# STM32.net
KiCad netlist of a schematic drawn in Altium Designer
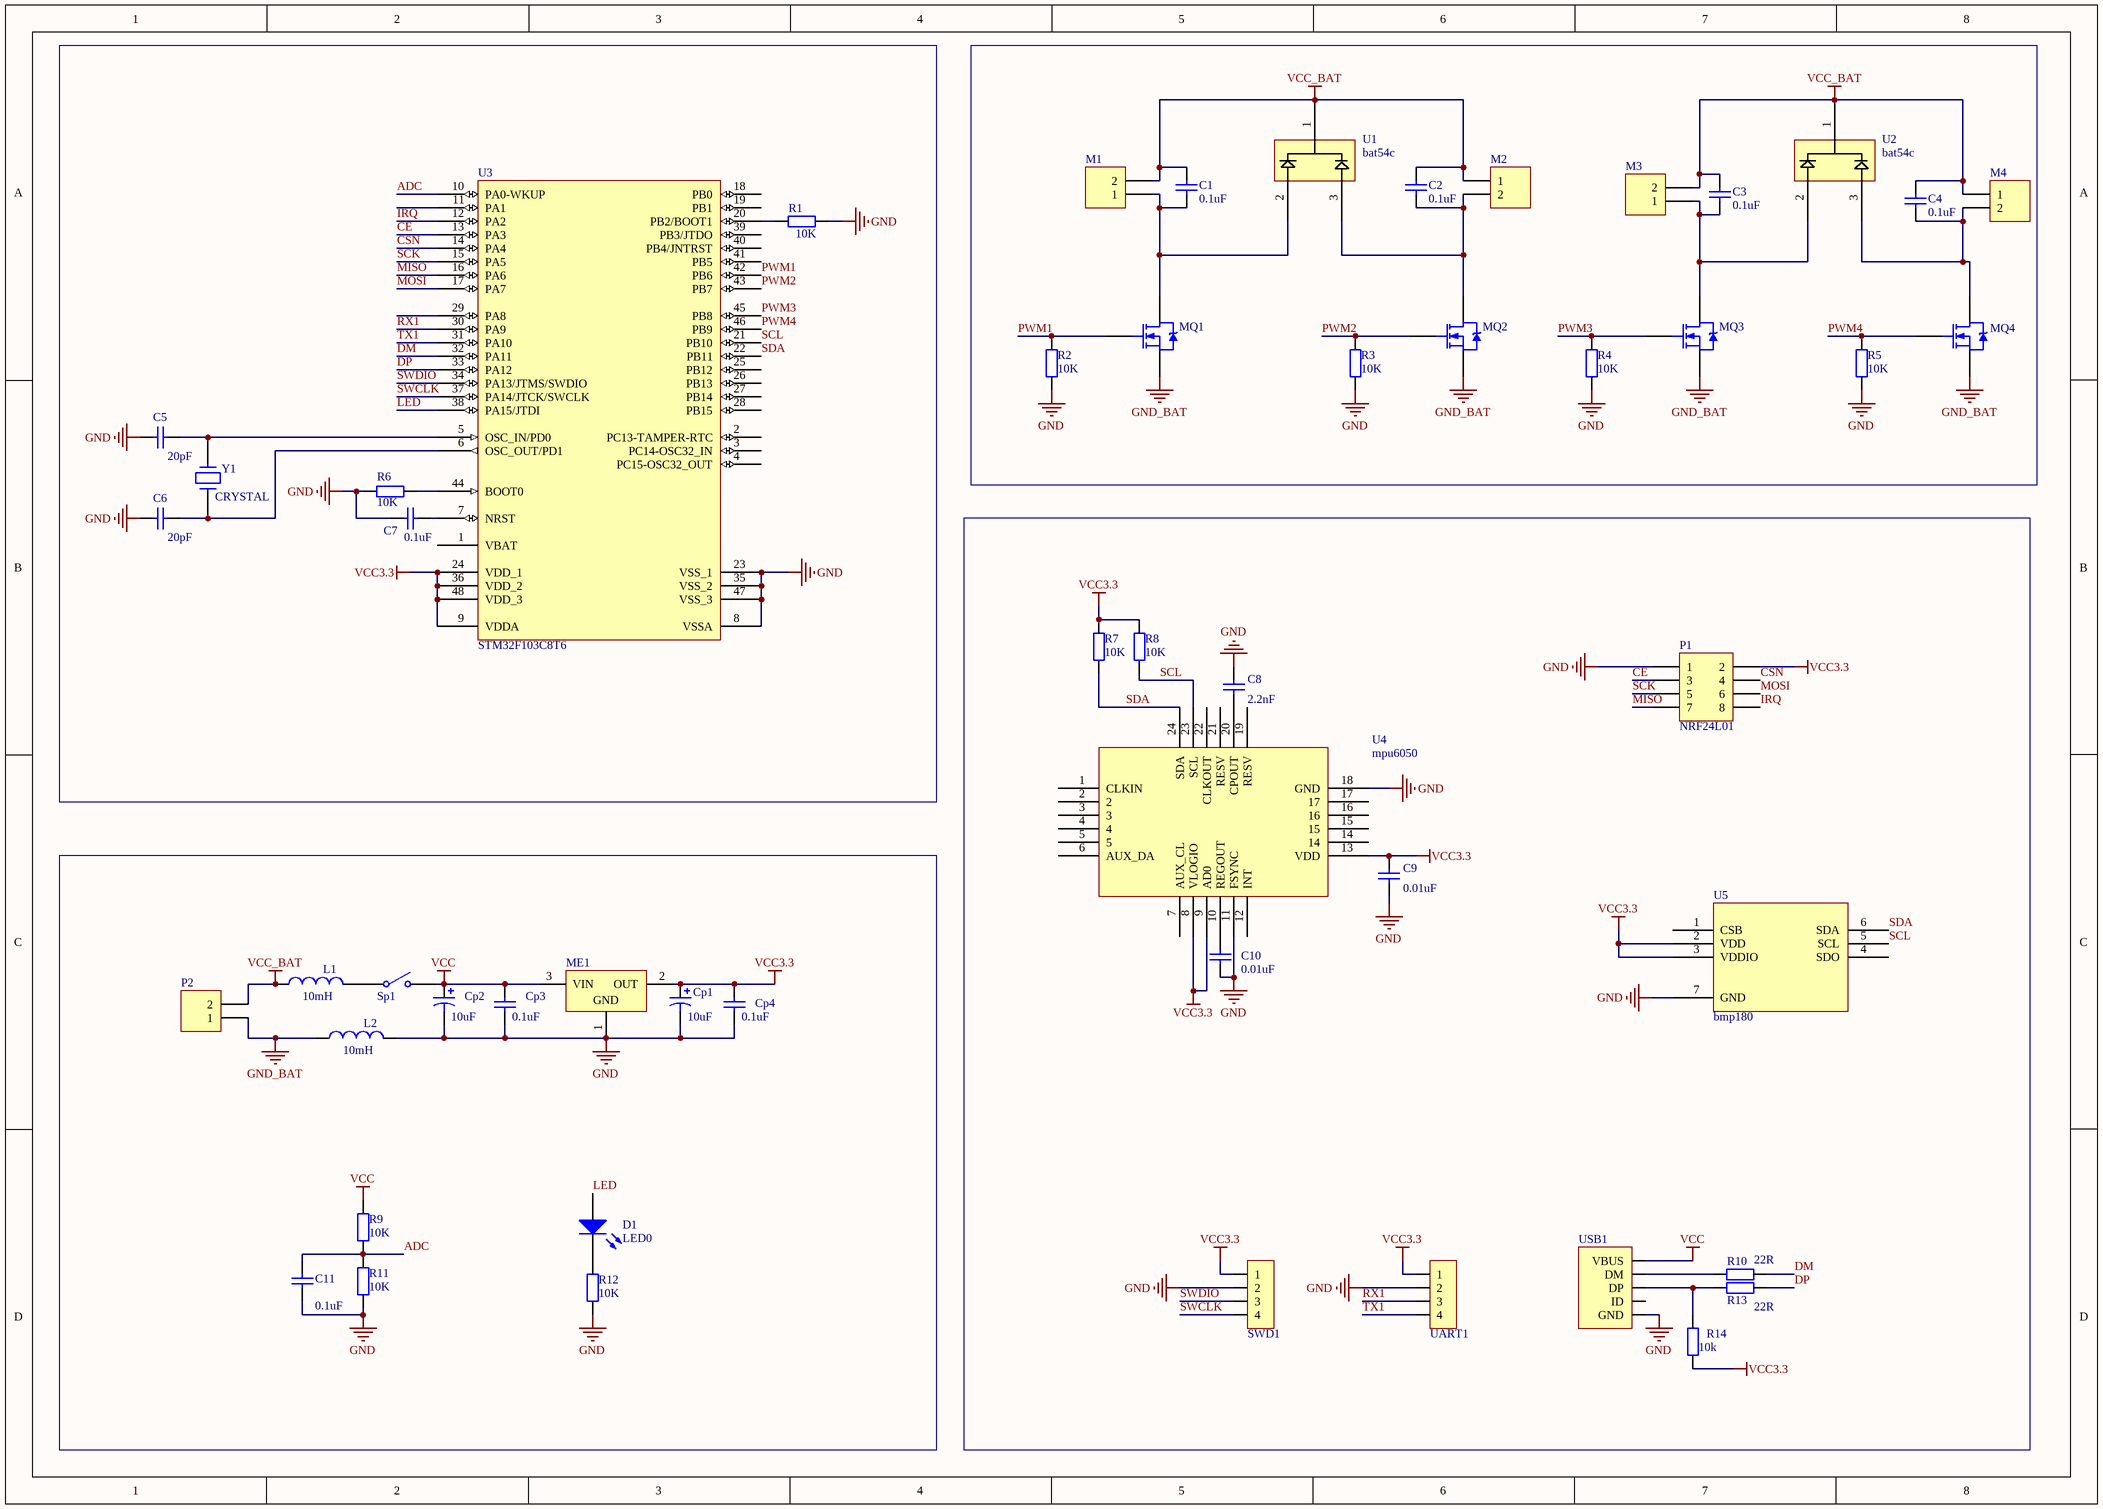
[diagram p0: STM32四轴.SchDoc]

(export (version "E")
  (design (tool "Eeschema 10.0.6"))
  (components
    (comp (ref "C1")
      (value "0.1uF")
      (footprint "0805s")
      (description "Capacitor")
      (fields (field (name "Comment") "Cap") (field (name "PUBLISHER") "Altium Limited"))
      (libsource (lib "Miscellaneous Devices") (part "Cap"))
    )
    (comp (ref "C2")
      (value "0.1uF")
      (footprint "0805s")
      (description "Capacitor")
      (fields (field (name "Comment") "Cap") (field (name "PUBLISHER") "Altium Limited"))
      (libsource (lib "Miscellaneous Devices") (part "Cap"))
    )
    (comp (ref "C3")
      (value "0.1uF")
      (footprint "0805s")
      (description "Capacitor")
      (fields (field (name "Comment") "Cap") (field (name "PUBLISHER") "Altium Limited"))
      (libsource (lib "Miscellaneous Devices") (part "Cap"))
    )
    (comp (ref "C4")
      (value "0.1uF")
      (footprint "0805s")
      (description "Capacitor")
      (fields (field (name "Comment") "Cap") (field (name "PUBLISHER") "Altium Limited"))
      (libsource (lib "Miscellaneous Devices") (part "Cap"))
    )
    (comp (ref "C5")
      (value "20pF")
      (footprint "0805s")
      (description "Capacitor")
      (fields (field (name "Comment") "Cap") (field (name "PUBLISHER") "Altium Limited"))
      (libsource (lib "Miscellaneous Devices") (part "Cap"))
    )
    (comp (ref "C6")
      (value "20pF")
      (footprint "0805s")
      (description "Capacitor")
      (fields (field (name "Comment") "Cap") (field (name "PUBLISHER") "Altium Limited"))
      (libsource (lib "Miscellaneous Devices") (part "Cap"))
    )
    (comp (ref "C7")
      (value "0.1uF")
      (footprint "0805s")
      (description "Capacitor")
      (fields (field (name "Comment") "Cap") (field (name "PUBLISHER") "Altium Limited"))
      (libsource (lib "Miscellaneous Devices") (part "Cap"))
    )
    (comp (ref "C8")
      (value "2.2nF")
      (footprint "0805s")
      (description "Capacitor")
      (fields (field (name "Comment") "Cap") (field (name "PUBLISHER") "Altium Limited"))
      (libsource (lib "Miscellaneous Devices") (part "Cap"))
    )
    (comp (ref "C9")
      (value "0.01uF")
      (footprint "0805s")
      (description "Capacitor")
      (fields (field (name "Comment") "Cap") (field (name "PUBLISHER") "Altium Limited"))
      (libsource (lib "Miscellaneous Devices") (part "Cap"))
    )
    (comp (ref "C10")
      (value "0.01uF")
      (footprint "0805s")
      (description "Capacitor")
      (fields (field (name "Comment") "Cap") (field (name "PUBLISHER") "Altium Limited"))
      (libsource (lib "Miscellaneous Devices") (part "Cap"))
    )
    (comp (ref "C11")
      (value "0.1uF")
      (footprint "0805s")
      (description "Capacitor")
      (fields (field (name "Comment") "Cap") (field (name "PUBLISHER") "Altium Limited"))
      (libsource (lib "Miscellaneous Devices") (part "Cap"))
    )
    (comp (ref "Cp1")
      (value "10uF")
      (footprint "3216")
      (description "Polarized Capacitor (Radial)")
      (fields (field (name "Comment") "Cap Pol1") (field (name "PUBLISHER") "Altium Limited"))
      (libsource (lib "Miscellaneous Devices") (part "Cap Pol1"))
    )
    (comp (ref "Cp2")
      (value "10uF")
      (footprint "3216")
      (description "Polarized Capacitor (Radial)")
      (fields (field (name "Comment") "Cap Pol1") (field (name "PUBLISHER") "Altium Limited"))
      (libsource (lib "Miscellaneous Devices") (part "Cap Pol1"))
    )
    (comp (ref "Cp3")
      (value "0.1uF")
      (footprint "0805s")
      (description "Capacitor")
      (fields (field (name "Comment") "Cap") (field (name "PUBLISHER") "Altium Limited"))
      (libsource (lib "Miscellaneous Devices") (part "Cap"))
    )
    (comp (ref "Cp4")
      (value "0.1uF")
      (footprint "0805s")
      (description "Capacitor")
      (fields (field (name "Comment") "Cap") (field (name "PUBLISHER") "Altium Limited"))
      (libsource (lib "Miscellaneous Devices") (part "Cap"))
    )
    (comp (ref "D1")
      (value "LED0")
      (footprint "0805s")
      (description "Typical INFRARED GaAs LED")
      (fields (field (name "PUBLISHER") "Altium Limited"))
      (libsource (lib "Miscellaneous Devices") (part "LED0"))
    )
    (comp (ref "L1")
      (value "10mH")
      (footprint "0805s")
      (description "Inductor")
      (fields (field (name "PUBLISHER") "Altium Limited"))
      (libsource (lib "Miscellaneous Devices") (part "Inductor"))
    )
    (comp (ref "L2")
      (value "10mH")
      (footprint "0805s")
      (description "Inductor")
      (fields (field (name "PUBLISHER") "Altium Limited"))
      (libsource (lib "Miscellaneous Devices") (part "Inductor"))
    )
    (comp (ref "M1")
      (value "Header 2")
      (footprint "0805s")
      (description "Header, 2-Pin")
      (fields (field (name "PUBLISHER") "Altium Limited"))
      (libsource (lib "") (part "Header 2_1"))
    )
    (comp (ref "M2")
      (value "Header 2")
      (footprint "0805s")
      (description "Header, 2-Pin")
      (fields (field (name "PUBLISHER") "Altium Limited"))
      (libsource (lib "Miscellaneous Connectors") (part "Header 2"))
    )
    (comp (ref "M3")
      (value "Header 2")
      (footprint "0805s")
      (description "Header, 2-Pin")
      (fields (field (name "PUBLISHER") "Altium Limited"))
      (libsource (lib "") (part "Header 2_1"))
    )
    (comp (ref "M4")
      (value "Header 2")
      (footprint "0805s")
      (description "Header, 2-Pin")
      (fields (field (name "PUBLISHER") "Altium Limited"))
      (libsource (lib "Miscellaneous Connectors") (part "Header 2"))
    )
    (comp (ref "ME1")
      (value "Volt Reg")
      (footprint "SOT-23")
      (description "Voltage Regulator")
      (fields (field (name "PUBLISHER") "Altium Limited"))
      (libsource (lib "Miscellaneous Devices") (part "Volt Reg"))
    )
    (comp (ref "MQ1")
      (value "NMOS-2")
      (footprint "SOT-23")
      (description "N-Channel Power MOSFET")
      (fields (field (name "PUBLISHER") "Altium Limited"))
      (libsource (lib "Miscellaneous Devices") (part "NMOS-2"))
    )
    (comp (ref "MQ2")
      (value "NMOS-2")
      (footprint "SOT-23")
      (description "N-Channel Power MOSFET")
      (fields (field (name "PUBLISHER") "Altium Limited"))
      (libsource (lib "Miscellaneous Devices") (part "NMOS-2"))
    )
    (comp (ref "MQ3")
      (value "NMOS-2")
      (footprint "SOT-23")
      (description "N-Channel Power MOSFET")
      (fields (field (name "PUBLISHER") "Altium Limited"))
      (libsource (lib "Miscellaneous Devices") (part "NMOS-2"))
    )
    (comp (ref "MQ4")
      (value "NMOS-2")
      (footprint "SOT-23")
      (description "N-Channel Power MOSFET")
      (fields (field (name "PUBLISHER") "Altium Limited"))
      (libsource (lib "Miscellaneous Devices") (part "NMOS-2"))
    )
    (comp (ref "P1")
      (value "NRF24L01")
      (footprint "HDR2X4")
      (description "Header, 4-Pin, Dual row")
      (fields (field (name "PUBLISHER") "Altium Limited"))
      (libsource (lib "Miscellaneous Connectors") (part "MHDR2X4"))
    )
    (comp (ref "P2")
      (value "Header 2")
      (footprint "SIP2")
      (description "Header, 2-Pin")
      (fields (field (name "PUBLISHER") "Altium Limited"))
      (libsource (lib "") (part "Header 2_1"))
    )
    (comp (ref "R1")
      (value "10K")
      (footprint "0805s")
      (description "Resistor")
      (fields (field (name "Comment") "Res2") (field (name "PUBLISHER") "Altium Limited"))
      (libsource (lib "") (part "Res2_1"))
    )
    (comp (ref "R2")
      (value "10K")
      (footprint "0805s")
      (description "Resistor")
      (fields (field (name "Comment") "Res2") (field (name "PUBLISHER") "Altium Limited"))
      (libsource (lib "") (part "Res2_2"))
    )
    (comp (ref "R3")
      (value "10K")
      (footprint "0805s")
      (description "Resistor")
      (fields (field (name "Comment") "Res2") (field (name "PUBLISHER") "Altium Limited"))
      (libsource (lib "") (part "Res2_2"))
    )
    (comp (ref "R4")
      (value "10K")
      (footprint "0805s")
      (description "Resistor")
      (fields (field (name "Comment") "Res2") (field (name "PUBLISHER") "Altium Limited"))
      (libsource (lib "") (part "Res2_2"))
    )
    (comp (ref "R5")
      (value "10K")
      (footprint "0805s")
      (description "Resistor")
      (fields (field (name "Comment") "Res2") (field (name "PUBLISHER") "Altium Limited"))
      (libsource (lib "") (part "Res2_2"))
    )
    (comp (ref "R6")
      (value "10K")
      (footprint "0805s")
      (description "Resistor")
      (fields (field (name "Comment") "Res2") (field (name "PUBLISHER") "Altium Limited"))
      (libsource (lib "") (part "Res2_3"))
    )
    (comp (ref "R7")
      (value "10K")
      (footprint "0805s")
      (description "Resistor")
      (fields (field (name "Comment") "Res2") (field (name "PUBLISHER") "Altium Limited"))
      (libsource (lib "Miscellaneous Devices") (part "Res2"))
    )
    (comp (ref "R8")
      (value "10K")
      (footprint "0805s")
      (description "Resistor")
      (fields (field (name "Comment") "Res2") (field (name "PUBLISHER") "Altium Limited"))
      (libsource (lib "Miscellaneous Devices") (part "Res2"))
    )
    (comp (ref "R9")
      (value "10K")
      (footprint "0805s")
      (description "Resistor")
      (fields (field (name "Comment") "Res2") (field (name "PUBLISHER") "Altium Limited"))
      (libsource (lib "Miscellaneous Devices") (part "Res2"))
    )
    (comp (ref "R10")
      (value "22R")
      (footprint "0805s")
      (description "Resistor")
      (fields (field (name "Comment") "Res_0603"))
      (libsource (lib "SCH_Passive") (part "Res_0603"))
    )
    (comp (ref "R11")
      (value "10K")
      (footprint "0805s")
      (description "Resistor")
      (fields (field (name "Comment") "Res2") (field (name "PUBLISHER") "Altium Limited"))
      (libsource (lib "Miscellaneous Devices") (part "Res2"))
    )
    (comp (ref "R12")
      (value "10K")
      (footprint "0805s")
      (description "Resistor")
      (fields (field (name "Comment") "Res2") (field (name "PUBLISHER") "Altium Limited"))
      (libsource (lib "Miscellaneous Devices") (part "Res2"))
    )
    (comp (ref "R13")
      (value "22R")
      (footprint "0805s")
      (description "Resistor")
      (fields (field (name "Comment") "Res_0603"))
      (libsource (lib "SCH_Passive") (part "Res_0603"))
    )
    (comp (ref "R14")
      (value "10k")
      (footprint "常用元件封装:0805s")
      (description "Resistor")
      (fields (field (name "Comment") "Res_0603"))
      (libsource (lib "") (part "Res_0603_1"))
    )
    (comp (ref "Sp1")
      (value "SW-SPST")
      (footprint "SIP3")
      (description "Single-Pole, Single-Throw Switch")
      (fields (field (name "PUBLISHER") "Altium Limited"))
      (libsource (lib "Miscellaneous Devices") (part "SW-SPST"))
    )
    (comp (ref "SWD1")
      (value "HDR1X4_180_2.54")
      (footprint "SIP4")
      (description "Header")
      (libsource (lib "SCH_Connector") (part "HDR1X4_180_2.54"))
    )
    (comp (ref "U1") (value "bat54c") (footprint "SOT-23") (libsource (lib "四轴") (part "bat54c")))
    (comp (ref "U2") (value "bat54c") (footprint "SOT-23") (libsource (lib "四轴") (part "bat54c")))
    (comp (ref "U3")
      (value "STM32F103C8T6")
      (footprint "LQFP48")
      (description "STM32 ARM-based 32-bit MCU with 64 Kbytes Flash, 48-pin LQFP, Industrial Temperature")
      (fields (field (name "PUBLISHER") "Altium Limited"))
      (libsource (lib "ST Microcontroller 32-Bit STM32") (part "STM32F103C8T6"))
    )
    (comp (ref "U4") (value "mpu6050") (footprint "MPU6050") (libsource (lib "四轴") (part "mpu6050")))
    (comp (ref "U5") (value "bmp180") (footprint "LCC8") (libsource (lib "四轴") (part "bmp180")))
    (comp (ref "UART1")
      (value "HDR1X4_180_2.54")
      (footprint "SIP4")
      (description "Header")
      (libsource (lib "SCH_Connector") (part "HDR1X4_180_2.54"))
    )
    (comp (ref "USB1")
      (value "USB_Micro")
      (footprint "MICRO-USB")
      (description "USB")
      (libsource (lib "SCH_USB") (part "USB_Micro"))
    )
    (comp (ref "Y1")
      (value "CRYSTAL")
      (footprint "SIP2")
      (description "Crystal")
      (libsource (lib "杂元件库") (part "CRYSTAL"))
    )
  )
  (nets
    (net (code "1") (name "/ADC") (class "Default")
      (node (ref "C11") (pin "2") (pinfunction "2_2") (pintype "passive"))
      (node (ref "R11") (pin "2") (pinfunction "2_2") (pintype "passive"))
      (node (ref "R9") (pin "1") (pinfunction "1_1") (pintype "passive"))
      (node (ref "U3") (pin "10") (pinfunction "PA0-WKUP_10") (pintype "bidirectional"))
    )
    (net (code "2") (name "/CE") (class "Default")
      (node (ref "P1") (pin "3") (pinfunction "3_3") (pintype "passive"))
      (node (ref "U3") (pin "13") (pinfunction "PA3_13") (pintype "bidirectional"))
    )
    (net (code "3") (name "/CSN") (class "Default")
      (node (ref "P1") (pin "4") (pinfunction "4_4") (pintype "passive"))
      (node (ref "U3") (pin "14") (pinfunction "PA4_14") (pintype "bidirectional"))
    )
    (net (code "4") (name "/DM") (class "Default")
      (node (ref "R10") (pin "2") (pinfunction "2_2") (pintype "passive"))
      (node (ref "U3") (pin "32") (pinfunction "PA11_32") (pintype "bidirectional"))
    )
    (net (code "5") (name "/DP") (class "Default")
      (node (ref "R13") (pin "2") (pinfunction "2_2") (pintype "passive"))
      (node (ref "U3") (pin "33") (pinfunction "PA12_33") (pintype "bidirectional"))
    )
    (net (code "6") (name "/IRQ") (class "Default")
      (node (ref "P1") (pin "8") (pinfunction "8_8") (pintype "passive"))
      (node (ref "U3") (pin "12") (pinfunction "PA2_12") (pintype "bidirectional"))
    )
    (net (code "7") (name "/LED") (class "Default")
      (node (ref "D1") (pin "1") (pinfunction "A_1") (pintype "passive"))
      (node (ref "U3") (pin "38") (pinfunction "PA15/JTDI_38") (pintype "bidirectional"))
    )
    (net (code "8") (name "/MISO") (class "Default")
      (node (ref "P1") (pin "7") (pinfunction "7_7") (pintype "passive"))
      (node (ref "U3") (pin "16") (pinfunction "PA6_16") (pintype "bidirectional"))
    )
    (net (code "9") (name "/MOSI") (class "Default")
      (node (ref "P1") (pin "6") (pinfunction "6_6") (pintype "passive"))
      (node (ref "U3") (pin "17") (pinfunction "PA7_17") (pintype "bidirectional"))
    )
    (net (code "10") (name "/PWM1") (class "Default")
      (node (ref "MQ1") (pin "1") (pinfunction "G_1") (pintype "passive"))
      (node (ref "R2") (pin "1") (pinfunction "1_1") (pintype "passive"))
      (node (ref "U3") (pin "42") (pinfunction "PB6_42") (pintype "bidirectional"))
    )
    (net (code "11") (name "/PWM2") (class "Default")
      (node (ref "MQ2") (pin "1") (pinfunction "G_1") (pintype "passive"))
      (node (ref "R3") (pin "1") (pinfunction "1_1") (pintype "passive"))
      (node (ref "U3") (pin "43") (pinfunction "PB7_43") (pintype "bidirectional"))
    )
    (net (code "12") (name "/PWM3") (class "Default")
      (node (ref "MQ3") (pin "1") (pinfunction "G_1") (pintype "passive"))
      (node (ref "R4") (pin "1") (pinfunction "1_1") (pintype "passive"))
      (node (ref "U3") (pin "45") (pinfunction "PB8_45") (pintype "bidirectional"))
    )
    (net (code "13") (name "/PWM4") (class "Default")
      (node (ref "MQ4") (pin "1") (pinfunction "G_1") (pintype "passive"))
      (node (ref "R5") (pin "1") (pinfunction "1_1") (pintype "passive"))
      (node (ref "U3") (pin "46") (pinfunction "PB9_46") (pintype "bidirectional"))
    )
    (net (code "14") (name "/RX1") (class "Default")
      (node (ref "U3") (pin "30") (pinfunction "PA9_30") (pintype "bidirectional"))
      (node (ref "UART1") (pin "3") (pinfunction "3_3") (pintype "passive"))
    )
    (net (code "15") (name "/SCK") (class "Default")
      (node (ref "P1") (pin "5") (pinfunction "5_5") (pintype "passive"))
      (node (ref "U3") (pin "15") (pinfunction "PA5_15") (pintype "bidirectional"))
    )
    (net (code "16") (name "/SCL") (class "Default")
      (node (ref "R8") (pin "1") (pinfunction "1_1") (pintype "passive"))
      (node (ref "U3") (pin "21") (pinfunction "PB10_21") (pintype "bidirectional"))
      (node (ref "U4") (pin "23") (pinfunction "SCL_23") (pintype "passive"))
      (node (ref "U5") (pin "5") (pinfunction "SCL_5") (pintype "passive"))
    )
    (net (code "17") (name "/SDA") (class "Default")
      (node (ref "R7") (pin "1") (pinfunction "1_1") (pintype "passive"))
      (node (ref "U3") (pin "22") (pinfunction "PB11_22") (pintype "bidirectional"))
      (node (ref "U4") (pin "24") (pinfunction "SDA_24") (pintype "passive"))
      (node (ref "U5") (pin "6") (pinfunction "SDA_6") (pintype "passive"))
    )
    (net (code "18") (name "/SWCLK") (class "Default")
      (node (ref "SWD1") (pin "4") (pinfunction "4_4") (pintype "passive"))
      (node (ref "U3") (pin "37") (pinfunction "PA14/JTCK/SWCLK_37") (pintype "bidirectional"))
    )
    (net (code "19") (name "/SWDIO") (class "Default")
      (node (ref "SWD1") (pin "3") (pinfunction "3_3") (pintype "passive"))
      (node (ref "U3") (pin "34") (pinfunction "PA13/JTMS/SWDIO_34") (pintype "bidirectional"))
    )
    (net (code "20") (name "/TX1") (class "Default")
      (node (ref "U3") (pin "31") (pinfunction "PA10_31") (pintype "bidirectional"))
      (node (ref "UART1") (pin "4") (pinfunction "4_4") (pintype "passive"))
    )
    (net (code "21") (name "GND") (class "Default")
      (node (ref "C10") (pin "1") (pinfunction "1_1") (pintype "passive"))
      (node (ref "C11") (pin "1") (pinfunction "1_1") (pintype "passive"))
      (node (ref "C5") (pin "1") (pinfunction "1_1") (pintype "passive"))
      (node (ref "C6") (pin "1") (pinfunction "1_1") (pintype "passive"))
      (node (ref "C7") (pin "1") (pinfunction "1_1") (pintype "passive"))
      (node (ref "C8") (pin "2") (pinfunction "2_2") (pintype "passive"))
      (node (ref "C9") (pin "1") (pinfunction "1_1") (pintype "passive"))
      (node (ref "Cp1") (pin "2") (pinfunction "2_2") (pintype "passive"))
      (node (ref "Cp2") (pin "2") (pinfunction "2_2") (pintype "passive"))
      (node (ref "Cp3") (pin "1") (pinfunction "1_1") (pintype "passive"))
      (node (ref "Cp4") (pin "1") (pinfunction "1_1") (pintype "passive"))
      (node (ref "L2") (pin "2") (pinfunction "2_2") (pintype "passive"))
      (node (ref "ME1") (pin "1") (pinfunction "GND_1") (pintype "passive"))
      (node (ref "P1") (pin "1") (pinfunction "1_1") (pintype "passive"))
      (node (ref "R1") (pin "2") (pinfunction "2_2") (pintype "passive"))
      (node (ref "R11") (pin "1") (pinfunction "1_1") (pintype "passive"))
      (node (ref "R12") (pin "1") (pinfunction "1_1") (pintype "passive"))
      (node (ref "R2") (pin "2") (pinfunction "2_2") (pintype "passive"))
      (node (ref "R3") (pin "2") (pinfunction "2_2") (pintype "passive"))
      (node (ref "R4") (pin "2") (pinfunction "2_2") (pintype "passive"))
      (node (ref "R5") (pin "2") (pinfunction "2_2") (pintype "passive"))
      (node (ref "R6") (pin "2") (pinfunction "2_2") (pintype "passive"))
      (node (ref "SWD1") (pin "2") (pinfunction "2_2") (pintype "passive"))
      (node (ref "U3") (pin "23") (pinfunction "VSS_1_23") (pintype "power_in"))
      (node (ref "U3") (pin "35") (pinfunction "VSS_2_35") (pintype "power_in"))
      (node (ref "U3") (pin "47") (pinfunction "VSS_3_47") (pintype "power_in"))
      (node (ref "U3") (pin "8") (pinfunction "VSSA_8") (pintype "power_in"))
      (node (ref "U4") (pin "11") (pinfunction "FSYNC_11") (pintype "passive"))
      (node (ref "U4") (pin "18") (pinfunction "GND_18") (pintype "passive"))
      (node (ref "U5") (pin "7") (pinfunction "GND_7") (pintype "passive"))
      (node (ref "UART1") (pin "2") (pinfunction "2_2") (pintype "passive"))
      (node (ref "USB1") (pin "5") (pinfunction "GND_5") (pintype "passive"))
    )
    (net (code "22") (name "GND_BAT") (class "Default")
      (node (ref "L2") (pin "1") (pinfunction "1_1") (pintype "passive"))
      (node (ref "MQ1") (pin "2") (pinfunction "S_2") (pintype "passive"))
      (node (ref "MQ2") (pin "2") (pinfunction "S_2") (pintype "passive"))
      (node (ref "MQ3") (pin "2") (pinfunction "S_2") (pintype "passive"))
      (node (ref "MQ4") (pin "2") (pinfunction "S_2") (pintype "passive"))
      (node (ref "P2") (pin "1") (pinfunction "1_1") (pintype "passive"))
    )
    (net (code "23") (name "Net-(D1-K)") (class "Default")
      (node (ref "D1") (pin "2") (pinfunction "K_2") (pintype "passive"))
      (node (ref "R12") (pin "2") (pinfunction "2_2") (pintype "passive"))
    )
    (net (code "24") (name "Net-(MQ1-D)") (class "Default")
      (node (ref "C1") (pin "2") (pinfunction "2_2") (pintype "passive"))
      (node (ref "M1") (pin "1") (pinfunction "1_1") (pintype "passive"))
      (node (ref "MQ1") (pin "3") (pinfunction "D_3") (pintype "passive"))
      (node (ref "U1") (pin "2") (pinfunction "2_2") (pintype "passive"))
    )
    (net (code "25") (name "Net-(MQ2-D)") (class "Default")
      (node (ref "C2") (pin "2") (pinfunction "2_2") (pintype "passive"))
      (node (ref "M2") (pin "2") (pinfunction "2_2") (pintype "passive"))
      (node (ref "MQ2") (pin "3") (pinfunction "D_3") (pintype "passive"))
      (node (ref "U1") (pin "3") (pinfunction "3_3") (pintype "passive"))
    )
    (net (code "26") (name "Net-(MQ3-D)") (class "Default")
      (node (ref "C3") (pin "2") (pinfunction "2_2") (pintype "passive"))
      (node (ref "M3") (pin "1") (pinfunction "1_1") (pintype "passive"))
      (node (ref "MQ3") (pin "3") (pinfunction "D_3") (pintype "passive"))
      (node (ref "U2") (pin "2") (pinfunction "2_2") (pintype "passive"))
    )
    (net (code "27") (name "Net-(MQ4-D)") (class "Default")
      (node (ref "C4") (pin "2") (pinfunction "2_2") (pintype "passive"))
      (node (ref "M4") (pin "2") (pinfunction "2_2") (pintype "passive"))
      (node (ref "MQ4") (pin "3") (pinfunction "D_3") (pintype "passive"))
      (node (ref "U2") (pin "3") (pinfunction "3_3") (pintype "passive"))
    )
    (net (code "28") (name "Net-(Sp1-COMMON)") (class "Default")
      (node (ref "L1") (pin "2") (pinfunction "2_2") (pintype "passive"))
      (node (ref "Sp1") (pin "1") (pinfunction "COMMON_1") (pintype "passive"))
    )
    (net (code "29") (name "Net-(U3-BOOT0)") (class "Default")
      (node (ref "R6") (pin "1") (pinfunction "1_1") (pintype "passive"))
      (node (ref "U3") (pin "44") (pinfunction "BOOT0_44") (pintype "input"))
    )
    (net (code "30") (name "Net-(U3-NRST)") (class "Default")
      (node (ref "C7") (pin "2") (pinfunction "2_2") (pintype "passive"))
      (node (ref "U3") (pin "7") (pinfunction "NRST_7") (pintype "bidirectional"))
    )
    (net (code "31") (name "Net-(U3-OSC_IN{slash}PD0)") (class "Default")
      (node (ref "C5") (pin "2") (pinfunction "2_2") (pintype "passive"))
      (node (ref "U3") (pin "5") (pinfunction "OSC_IN/PD0_5") (pintype "input"))
      (node (ref "Y1") (pin "2") (pinfunction "2_2") (pintype "passive"))
    )
    (net (code "32") (name "Net-(U3-OSC_OUT{slash}PD1)") (class "Default")
      (node (ref "C6") (pin "2") (pinfunction "2_2") (pintype "passive"))
      (node (ref "U3") (pin "6") (pinfunction "OSC_OUT/PD1_6") (pintype "output"))
      (node (ref "Y1") (pin "1") (pinfunction "1_1") (pintype "passive"))
    )
    (net (code "33") (name "Net-(U3-PB2{slash}BOOT1)") (class "Default")
      (node (ref "R1") (pin "1") (pinfunction "1_1") (pintype "passive"))
      (node (ref "U3") (pin "20") (pinfunction "PB2/BOOT1_20") (pintype "bidirectional"))
    )
    (net (code "34") (name "Net-(U4-CPOUT)") (class "Default")
      (node (ref "C8") (pin "1") (pinfunction "1_1") (pintype "passive"))
      (node (ref "U4") (pin "20") (pinfunction "CPOUT_20") (pintype "passive"))
    )
    (net (code "35") (name "Net-(U4-REGOUT)") (class "Default")
      (node (ref "C10") (pin "2") (pinfunction "2_2") (pintype "passive"))
      (node (ref "U4") (pin "10") (pinfunction "REGOUT_10") (pintype "passive"))
    )
    (net (code "36") (name "Net-(USB1-DM)") (class "Default")
      (node (ref "R10") (pin "1") (pinfunction "1_1") (pintype "passive"))
      (node (ref "USB1") (pin "2") (pinfunction "DM_2") (pintype "passive"))
    )
    (net (code "37") (name "Net-(USB1-DP)") (class "Default")
      (node (ref "R13") (pin "1") (pinfunction "1_1") (pintype "passive"))
      (node (ref "R14") (pin "1") (pinfunction "1_1") (pintype "passive"))
      (node (ref "USB1") (pin "3") (pinfunction "DP_3") (pintype "passive"))
    )
    (net (code "38") (name "VCC") (class "Default")
      (node (ref "Cp2") (pin "1") (pinfunction "1_1") (pintype "passive"))
      (node (ref "Cp3") (pin "2") (pinfunction "2_2") (pintype "passive"))
      (node (ref "ME1") (pin "3") (pinfunction "VIN_3") (pintype "passive"))
      (node (ref "R9") (pin "2") (pinfunction "2_2") (pintype "passive"))
      (node (ref "Sp1") (pin "2") (pinfunction "NO_2") (pintype "passive"))
      (node (ref "USB1") (pin "1") (pinfunction "VBUS_1") (pintype "passive"))
    )
    (net (code "39") (name "VCC3.3") (class "Default")
      (node (ref "C9") (pin "2") (pinfunction "2_2") (pintype "passive"))
      (node (ref "Cp1") (pin "1") (pinfunction "1_1") (pintype "passive"))
      (node (ref "Cp4") (pin "2") (pinfunction "2_2") (pintype "passive"))
      (node (ref "ME1") (pin "2") (pinfunction "OUT_2") (pintype "passive"))
      (node (ref "P1") (pin "2") (pinfunction "2_2") (pintype "passive"))
      (node (ref "R14") (pin "2") (pinfunction "2_2") (pintype "passive"))
      (node (ref "R7") (pin "2") (pinfunction "2_2") (pintype "passive"))
      (node (ref "R8") (pin "2") (pinfunction "2_2") (pintype "passive"))
      (node (ref "SWD1") (pin "1") (pinfunction "1_1") (pintype "passive"))
      (node (ref "U3") (pin "24") (pinfunction "VDD_1_24") (pintype "power_in"))
      (node (ref "U3") (pin "36") (pinfunction "VDD_2_36") (pintype "power_in"))
      (node (ref "U3") (pin "48") (pinfunction "VDD_3_48") (pintype "power_in"))
      (node (ref "U3") (pin "9") (pinfunction "VDDA_9") (pintype "power_in"))
      (node (ref "U4") (pin "13") (pinfunction "VDD_13") (pintype "passive"))
      (node (ref "U4") (pin "8") (pinfunction "VLOGIO_8") (pintype "passive"))
      (node (ref "U4") (pin "9") (pinfunction "AD0_9") (pintype "passive"))
      (node (ref "U5") (pin "2") (pinfunction "VDD_2") (pintype "passive"))
      (node (ref "U5") (pin "3") (pinfunction "VDDIO_3") (pintype "passive"))
      (node (ref "UART1") (pin "1") (pinfunction "1_1") (pintype "passive"))
    )
    (net (code "40") (name "VCC_BAT") (class "Default")
      (node (ref "C1") (pin "1") (pinfunction "1_1") (pintype "passive"))
      (node (ref "C2") (pin "1") (pinfunction "1_1") (pintype "passive"))
      (node (ref "C3") (pin "1") (pinfunction "1_1") (pintype "passive"))
      (node (ref "C4") (pin "1") (pinfunction "1_1") (pintype "passive"))
      (node (ref "L1") (pin "1") (pinfunction "1_1") (pintype "passive"))
      (node (ref "M1") (pin "2") (pinfunction "2_2") (pintype "passive"))
      (node (ref "M2") (pin "1") (pinfunction "1_1") (pintype "passive"))
      (node (ref "M3") (pin "2") (pinfunction "2_2") (pintype "passive"))
      (node (ref "M4") (pin "1") (pinfunction "1_1") (pintype "passive"))
      (node (ref "P2") (pin "2") (pinfunction "2_2") (pintype "passive"))
      (node (ref "U1") (pin "1") (pinfunction "1_1") (pintype "passive"))
      (node (ref "U2") (pin "1") (pinfunction "1_1") (pintype "passive"))
    )
    (net (code "41") (name "unconnected-(U3-PA1-Pad11)") (class "Default")
      (node (ref "U3") (pin "11") (pinfunction "PA1_11") (pintype "bidirectional"))
    )
    (net (code "42") (name "unconnected-(U3-PA8-Pad29)") (class "Default")
      (node (ref "U3") (pin "29") (pinfunction "PA8_29") (pintype "bidirectional"))
    )
    (net (code "43") (name "unconnected-(U3-PB0-Pad18)") (class "Default")
      (node (ref "U3") (pin "18") (pinfunction "PB0_18") (pintype "bidirectional"))
    )
    (net (code "44") (name "unconnected-(U3-PB1-Pad19)") (class "Default")
      (node (ref "U3") (pin "19") (pinfunction "PB1_19") (pintype "bidirectional"))
    )
    (net (code "45") (name "unconnected-(U3-PB3{slash}JTDO-Pad39)") (class "Default")
      (node (ref "U3") (pin "39") (pinfunction "PB3/JTDO_39") (pintype "bidirectional"))
    )
    (net (code "46") (name "unconnected-(U3-PB4{slash}JNTRST-Pad40)") (class "Default")
      (node (ref "U3") (pin "40") (pinfunction "PB4/JNTRST_40") (pintype "bidirectional"))
    )
    (net (code "47") (name "unconnected-(U3-PB5-Pad41)") (class "Default")
      (node (ref "U3") (pin "41") (pinfunction "PB5_41") (pintype "bidirectional"))
    )
    (net (code "48") (name "unconnected-(U3-PB12-Pad25)") (class "Default")
      (node (ref "U3") (pin "25") (pinfunction "PB12_25") (pintype "bidirectional"))
    )
    (net (code "49") (name "unconnected-(U3-PB13-Pad26)") (class "Default")
      (node (ref "U3") (pin "26") (pinfunction "PB13_26") (pintype "bidirectional"))
    )
    (net (code "50") (name "unconnected-(U3-PB14-Pad27)") (class "Default")
      (node (ref "U3") (pin "27") (pinfunction "PB14_27") (pintype "bidirectional"))
    )
    (net (code "51") (name "unconnected-(U3-PB15-Pad28)") (class "Default")
      (node (ref "U3") (pin "28") (pinfunction "PB15_28") (pintype "bidirectional"))
    )
    (net (code "52") (name "unconnected-(U3-PC13-TAMPER-RTC-Pad2)") (class "Default")
      (node (ref "U3") (pin "2") (pinfunction "PC13-TAMPER-RTC_2") (pintype "bidirectional"))
    )
    (net (code "53") (name "unconnected-(U3-PC14-OSC32_IN-Pad3)") (class "Default")
      (node (ref "U3") (pin "3") (pinfunction "PC14-OSC32_IN_3") (pintype "bidirectional"))
    )
    (net (code "54") (name "unconnected-(U3-PC15-OSC32_OUT-Pad4)") (class "Default")
      (node (ref "U3") (pin "4") (pinfunction "PC15-OSC32_OUT_4") (pintype "bidirectional"))
    )
    (net (code "55") (name "unconnected-(U3-VBAT-Pad1)") (class "Default")
      (node (ref "U3") (pin "1") (pinfunction "VBAT_1") (pintype "power_in"))
    )
    (net (code "56") (name "unconnected-(U4-AUX_CL-Pad7)") (class "Default")
      (node (ref "U4") (pin "7") (pinfunction "AUX_CL_7") (pintype "passive"))
    )
    (net (code "57") (name "unconnected-(U4-AUX_DA-Pad6)") (class "Default")
      (node (ref "U4") (pin "6") (pinfunction "AUX_DA_6") (pintype "passive"))
    )
    (net (code "58") (name "unconnected-(U4-CLKIN-Pad1)") (class "Default")
      (node (ref "U4") (pin "1") (pinfunction "CLKIN_1") (pintype "passive"))
    )
    (net (code "59") (name "unconnected-(U4-CLKOUT-Pad22)") (class "Default")
      (node (ref "U4") (pin "22") (pinfunction "CLKOUT_22") (pintype "passive"))
    )
    (net (code "60") (name "unconnected-(U4-INT-Pad12)") (class "Default")
      (node (ref "U4") (pin "12") (pinfunction "INT_12") (pintype "passive"))
    )
    (net (code "61") (name "unconnected-(U4-Pad2)") (class "Default")
      (node (ref "U4") (pin "2") (pinfunction "2_2") (pintype "passive"))
    )
    (net (code "62") (name "unconnected-(U4-Pad3)") (class "Default")
      (node (ref "U4") (pin "3") (pinfunction "3_3") (pintype "passive"))
    )
    (net (code "63") (name "unconnected-(U4-Pad4)") (class "Default")
      (node (ref "U4") (pin "4") (pinfunction "4_4") (pintype "passive"))
    )
    (net (code "64") (name "unconnected-(U4-Pad5)") (class "Default")
      (node (ref "U4") (pin "5") (pinfunction "5_5") (pintype "passive"))
    )
    (net (code "65") (name "unconnected-(U4-Pad14)") (class "Default")
      (node (ref "U4") (pin "14") (pinfunction "14_14") (pintype "passive"))
    )
    (net (code "66") (name "unconnected-(U4-Pad15)") (class "Default")
      (node (ref "U4") (pin "15") (pinfunction "15_15") (pintype "passive"))
    )
    (net (code "67") (name "unconnected-(U4-Pad16)") (class "Default")
      (node (ref "U4") (pin "16") (pinfunction "16_16") (pintype "passive"))
    )
    (net (code "68") (name "unconnected-(U4-Pad17)") (class "Default")
      (node (ref "U4") (pin "17") (pinfunction "17_17") (pintype "passive"))
    )
    (net (code "69") (name "unconnected-(U4-RESV-Pad19)") (class "Default")
      (node (ref "U4") (pin "19") (pinfunction "RESV_19") (pintype "passive"))
    )
    (net (code "70") (name "unconnected-(U4-RESV-Pad21)") (class "Default")
      (node (ref "U4") (pin "21") (pinfunction "RESV_21") (pintype "passive"))
    )
    (net (code "71") (name "unconnected-(U5-CSB-Pad1)") (class "Default")
      (node (ref "U5") (pin "1") (pinfunction "CSB_1") (pintype "passive"))
    )
    (net (code "72") (name "unconnected-(U5-SDO-Pad4)") (class "Default")
      (node (ref "U5") (pin "4") (pinfunction "SDO_4") (pintype "passive"))
    )
    (net (code "73") (name "unconnected-(USB1-ID-Pad4)") (class "Default")
      (node (ref "USB1") (pin "4") (pinfunction "ID_4") (pintype "passive"))
    )
  )
)
